# IsolationOut.net
KiCad netlist of a schematic drawn in Altium Designer
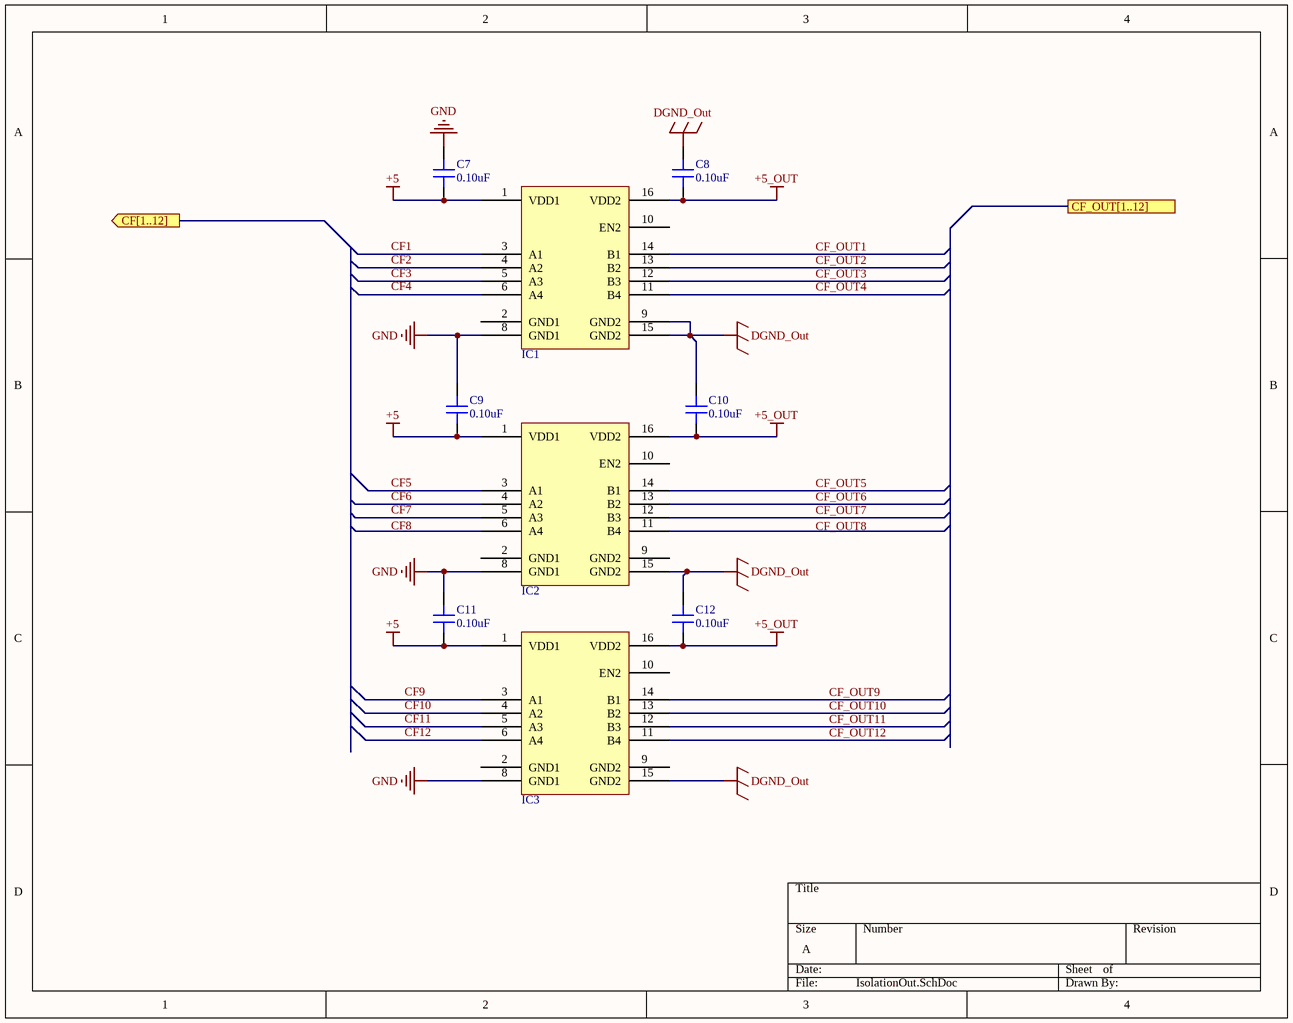
[diagram p0: IsolationOut.SchDoc]

(export (version "E")
  (design (tool "Eeschema 10.0.6"))
  (components
    (comp (ref "C7")
      (value "0.10uF")
      (footprint "CAP 0402/1005")
      (description "CAP CER 0.1UF 16V X7R 0402")
      (fields
        (field (name "PART NUMBER") "GRM155R71C104JA88D")
        (field (name "MANUFACTURER") "Murata Electronics North America")
      )
      (libsource (lib "Celestial Library Database") (part "Capacitor"))
    )
    (comp (ref "C8")
      (value "0.10uF")
      (footprint "CAP 0402/1005")
      (description "CAP CER 0.1UF 16V X7R 0402")
      (fields
        (field (name "PART NUMBER") "GRM155R71C104JA88D")
        (field (name "MANUFACTURER") "Murata Electronics North America")
      )
      (libsource (lib "Celestial Library Database") (part "Capacitor"))
    )
    (comp (ref "C9")
      (value "0.10uF")
      (footprint "CAP 0402/1005")
      (description "CAP CER 0.1UF 16V X7R 0402")
      (fields
        (field (name "PART NUMBER") "GRM155R71C104JA88D")
        (field (name "MANUFACTURER") "Murata Electronics North America")
      )
      (libsource (lib "Celestial Library Database") (part "Capacitor"))
    )
    (comp (ref "C10")
      (value "0.10uF")
      (footprint "CAP 0402/1005")
      (description "CAP CER 0.1UF 16V X7R 0402")
      (fields
        (field (name "PART NUMBER") "GRM155R71C104JA88D")
        (field (name "MANUFACTURER") "Murata Electronics North America")
      )
      (libsource (lib "Celestial Library Database") (part "Capacitor"))
    )
    (comp (ref "C11")
      (value "0.10uF")
      (footprint "CAP 0402/1005")
      (description "CAP CER 0.1UF 16V X7R 0402")
      (fields
        (field (name "PART NUMBER") "GRM155R71C104JA88D")
        (field (name "MANUFACTURER") "Murata Electronics North America")
      )
      (libsource (lib "Celestial Library Database") (part "Capacitor"))
    )
    (comp (ref "C12")
      (value "0.10uF")
      (footprint "CAP 0402/1005")
      (description "CAP CER 0.1UF 16V X7R 0402")
      (fields
        (field (name "PART NUMBER") "GRM155R71C104JA88D")
        (field (name "MANUFACTURER") "Murata Electronics North America")
      )
      (libsource (lib "Celestial Library Database") (part "Capacitor"))
    )
    (comp (ref "IC1")
      (value "SI8640BD-B-IS")
      (footprint "SI LABS SOIC-16 WIDE")
      (description "DGTL ISO 5KV 4CH GEN PURP 16SOIC")
      (fields (field (name "MANUFACTURER") "Silicon Labs"))
      (libsource (lib "Celestial Library Database") (part "SI LABS SI8640"))
    )
    (comp (ref "IC2")
      (value "SI8640BD-B-IS")
      (footprint "SI LABS SOIC-16 WIDE")
      (description "DGTL ISO 5KV 4CH GEN PURP 16SOIC")
      (fields (field (name "MANUFACTURER") "Silicon Labs"))
      (libsource (lib "Celestial Library Database") (part "SI LABS SI8640"))
    )
    (comp (ref "IC3")
      (value "SI8640BD-B-IS")
      (footprint "SI LABS SOIC-16 WIDE")
      (description "DGTL ISO 5KV 4CH GEN PURP 16SOIC")
      (fields (field (name "MANUFACTURER") "Silicon Labs"))
      (libsource (lib "Celestial Library Database") (part "SI LABS SI8640"))
    )
  )
  (nets
    (net (code "1") (name "+5") (class "Default")
      (node (ref "C11") (pin "1") (pinfunction "1_1") (pintype "passive"))
      (node (ref "C7") (pin "1") (pinfunction "1_1") (pintype "passive"))
      (node (ref "C9") (pin "1") (pinfunction "1_1") (pintype "passive"))
      (node (ref "IC1") (pin "1") (pinfunction "VDD1_1") (pintype "passive"))
      (node (ref "IC2") (pin "1") (pinfunction "VDD1_1") (pintype "passive"))
      (node (ref "IC3") (pin "1") (pinfunction "VDD1_1") (pintype "passive"))
    )
    (net (code "2") (name "+5_OUT") (class "Default")
      (node (ref "C10") (pin "1") (pinfunction "1_1") (pintype "passive"))
      (node (ref "C12") (pin "1") (pinfunction "1_1") (pintype "passive"))
      (node (ref "C8") (pin "1") (pinfunction "1_1") (pintype "passive"))
      (node (ref "IC1") (pin "16") (pinfunction "VDD2_16") (pintype "passive"))
      (node (ref "IC2") (pin "16") (pinfunction "VDD2_16") (pintype "passive"))
      (node (ref "IC3") (pin "16") (pinfunction "VDD2_16") (pintype "passive"))
    )
    (net (code "3") (name "/CF1") (class "Default")
      (node (ref "IC1") (pin "3") (pinfunction "A1_3") (pintype "passive"))
    )
    (net (code "4") (name "/CF2") (class "Default")
      (node (ref "IC1") (pin "4") (pinfunction "A2_4") (pintype "passive"))
    )
    (net (code "5") (name "/CF3") (class "Default")
      (node (ref "IC1") (pin "5") (pinfunction "A3_5") (pintype "passive"))
    )
    (net (code "7") (name "/CF4") (class "Default")
      (node (ref "IC1") (pin "6") (pinfunction "A4_6") (pintype "passive"))
    )
    (net (code "8") (name "/CF5") (class "Default")
      (node (ref "IC2") (pin "3") (pinfunction "A1_3") (pintype "passive"))
    )
    (net (code "9") (name "/CF6") (class "Default")
      (node (ref "IC2") (pin "4") (pinfunction "A2_4") (pintype "passive"))
    )
    (net (code "11") (name "/CF7") (class "Default")
      (node (ref "IC2") (pin "5") (pinfunction "A3_5") (pintype "passive"))
    )
    (net (code "12") (name "/CF9") (class "Default")
      (node (ref "IC3") (pin "3") (pinfunction "A1_3") (pintype "passive"))
    )
    (net (code "13") (name "/CF10") (class "Default")
      (node (ref "IC3") (pin "4") (pinfunction "A2_4") (pintype "passive"))
    )
    (net (code "14") (name "/CF11") (class "Default")
      (node (ref "IC3") (pin "5") (pinfunction "A3_5") (pintype "passive"))
    )
    (net (code "19") (name "/CF12") (class "Default")
      (node (ref "IC3") (pin "6") (pinfunction "A4_6") (pintype "passive"))
    )
    (net (code "29") (name "/CF_OUT1") (class "Default")
      (node (ref "IC1") (pin "14") (pinfunction "B1_14") (pintype "passive"))
    )
    (net (code "30") (name "/CF_OUT2") (class "Default")
      (node (ref "IC1") (pin "13") (pinfunction "B2_13") (pintype "passive"))
    )
    (net (code "31") (name "/CF_OUT3") (class "Default")
      (node (ref "IC1") (pin "12") (pinfunction "B3_12") (pintype "passive"))
    )
    (net (code "32") (name "/CF_OUT4") (class "Default")
      (node (ref "IC1") (pin "11") (pinfunction "B4_11") (pintype "passive"))
    )
    (net (code "33") (name "/CF_OUT5") (class "Default")
      (node (ref "IC2") (pin "14") (pinfunction "B1_14") (pintype "passive"))
    )
    (net (code "34") (name "/CF_OUT6") (class "Default")
      (node (ref "IC2") (pin "13") (pinfunction "B2_13") (pintype "passive"))
    )
    (net (code "35") (name "/CF_OUT7") (class "Default")
      (node (ref "IC2") (pin "12") (pinfunction "B3_12") (pintype "passive"))
    )
    (net (code "36") (name "/CF_OUT9") (class "Default")
      (node (ref "IC3") (pin "14") (pinfunction "B1_14") (pintype "passive"))
    )
    (net (code "37") (name "/CF_OUT10") (class "Default")
      (node (ref "IC3") (pin "13") (pinfunction "B2_13") (pintype "passive"))
    )
    (net (code "38") (name "/CF_OUT11") (class "Default")
      (node (ref "IC3") (pin "12") (pinfunction "B3_12") (pintype "passive"))
    )
    (net (code "39") (name "/CF_OUT12") (class "Default")
      (node (ref "IC3") (pin "11") (pinfunction "B4_11") (pintype "passive"))
    )
    (net (code "40") (name "DGND_Out") (class "Default")
      (node (ref "C10") (pin "2") (pinfunction "2_2") (pintype "passive"))
      (node (ref "C12") (pin "2") (pinfunction "2_2") (pintype "passive"))
      (node (ref "C8") (pin "2") (pinfunction "2_2") (pintype "passive"))
      (node (ref "IC1") (pin "15") (pinfunction "GND2_15") (pintype "passive"))
      (node (ref "IC1") (pin "9") (pinfunction "GND2_9") (pintype "passive"))
      (node (ref "IC2") (pin "15") (pinfunction "GND2_15") (pintype "passive"))
      (node (ref "IC3") (pin "15") (pinfunction "GND2_15") (pintype "passive"))
    )
    (net (code "41") (name "GND") (class "Default")
      (node (ref "C11") (pin "2") (pinfunction "2_2") (pintype "passive"))
      (node (ref "C7") (pin "2") (pinfunction "2_2") (pintype "passive"))
      (node (ref "C9") (pin "2") (pinfunction "2_2") (pintype "passive"))
      (node (ref "IC1") (pin "8") (pinfunction "GND1_8") (pintype "passive"))
      (node (ref "IC2") (pin "8") (pinfunction "GND1_8") (pintype "passive"))
      (node (ref "IC3") (pin "8") (pinfunction "GND1_8") (pintype "passive"))
    )
    (net (code "42") (name "unconnected-(IC1-EN2-Pad10)") (class "Default")
      (node (ref "IC1") (pin "10") (pinfunction "EN2_10") (pintype "passive"))
    )
    (net (code "43") (name "unconnected-(IC1-GND1-Pad2)") (class "Default")
      (node (ref "IC1") (pin "2") (pinfunction "GND1_2") (pintype "passive"))
    )
    (net (code "44") (name "unconnected-(IC2-A4-Pad6)") (class "Default")
      (node (ref "IC2") (pin "6") (pinfunction "A4_6") (pintype "passive"))
    )
    (net (code "45") (name "unconnected-(IC2-B4-Pad11)") (class "Default")
      (node (ref "IC2") (pin "11") (pinfunction "B4_11") (pintype "passive"))
    )
    (net (code "46") (name "unconnected-(IC2-EN2-Pad10)") (class "Default")
      (node (ref "IC2") (pin "10") (pinfunction "EN2_10") (pintype "passive"))
    )
    (net (code "47") (name "unconnected-(IC2-GND1-Pad2)") (class "Default")
      (node (ref "IC2") (pin "2") (pinfunction "GND1_2") (pintype "passive"))
    )
    (net (code "48") (name "unconnected-(IC2-GND2-Pad9)") (class "Default")
      (node (ref "IC2") (pin "9") (pinfunction "GND2_9") (pintype "passive"))
    )
    (net (code "49") (name "unconnected-(IC3-EN2-Pad10)") (class "Default")
      (node (ref "IC3") (pin "10") (pinfunction "EN2_10") (pintype "passive"))
    )
    (net (code "50") (name "unconnected-(IC3-GND1-Pad2)") (class "Default")
      (node (ref "IC3") (pin "2") (pinfunction "GND1_2") (pintype "passive"))
    )
    (net (code "51") (name "unconnected-(IC3-GND2-Pad9)") (class "Default")
      (node (ref "IC3") (pin "9") (pinfunction "GND2_9") (pintype "passive"))
    )
  )
)
